# DriverPanel.net
KiCad netlist of a schematic drawn in EAGLE
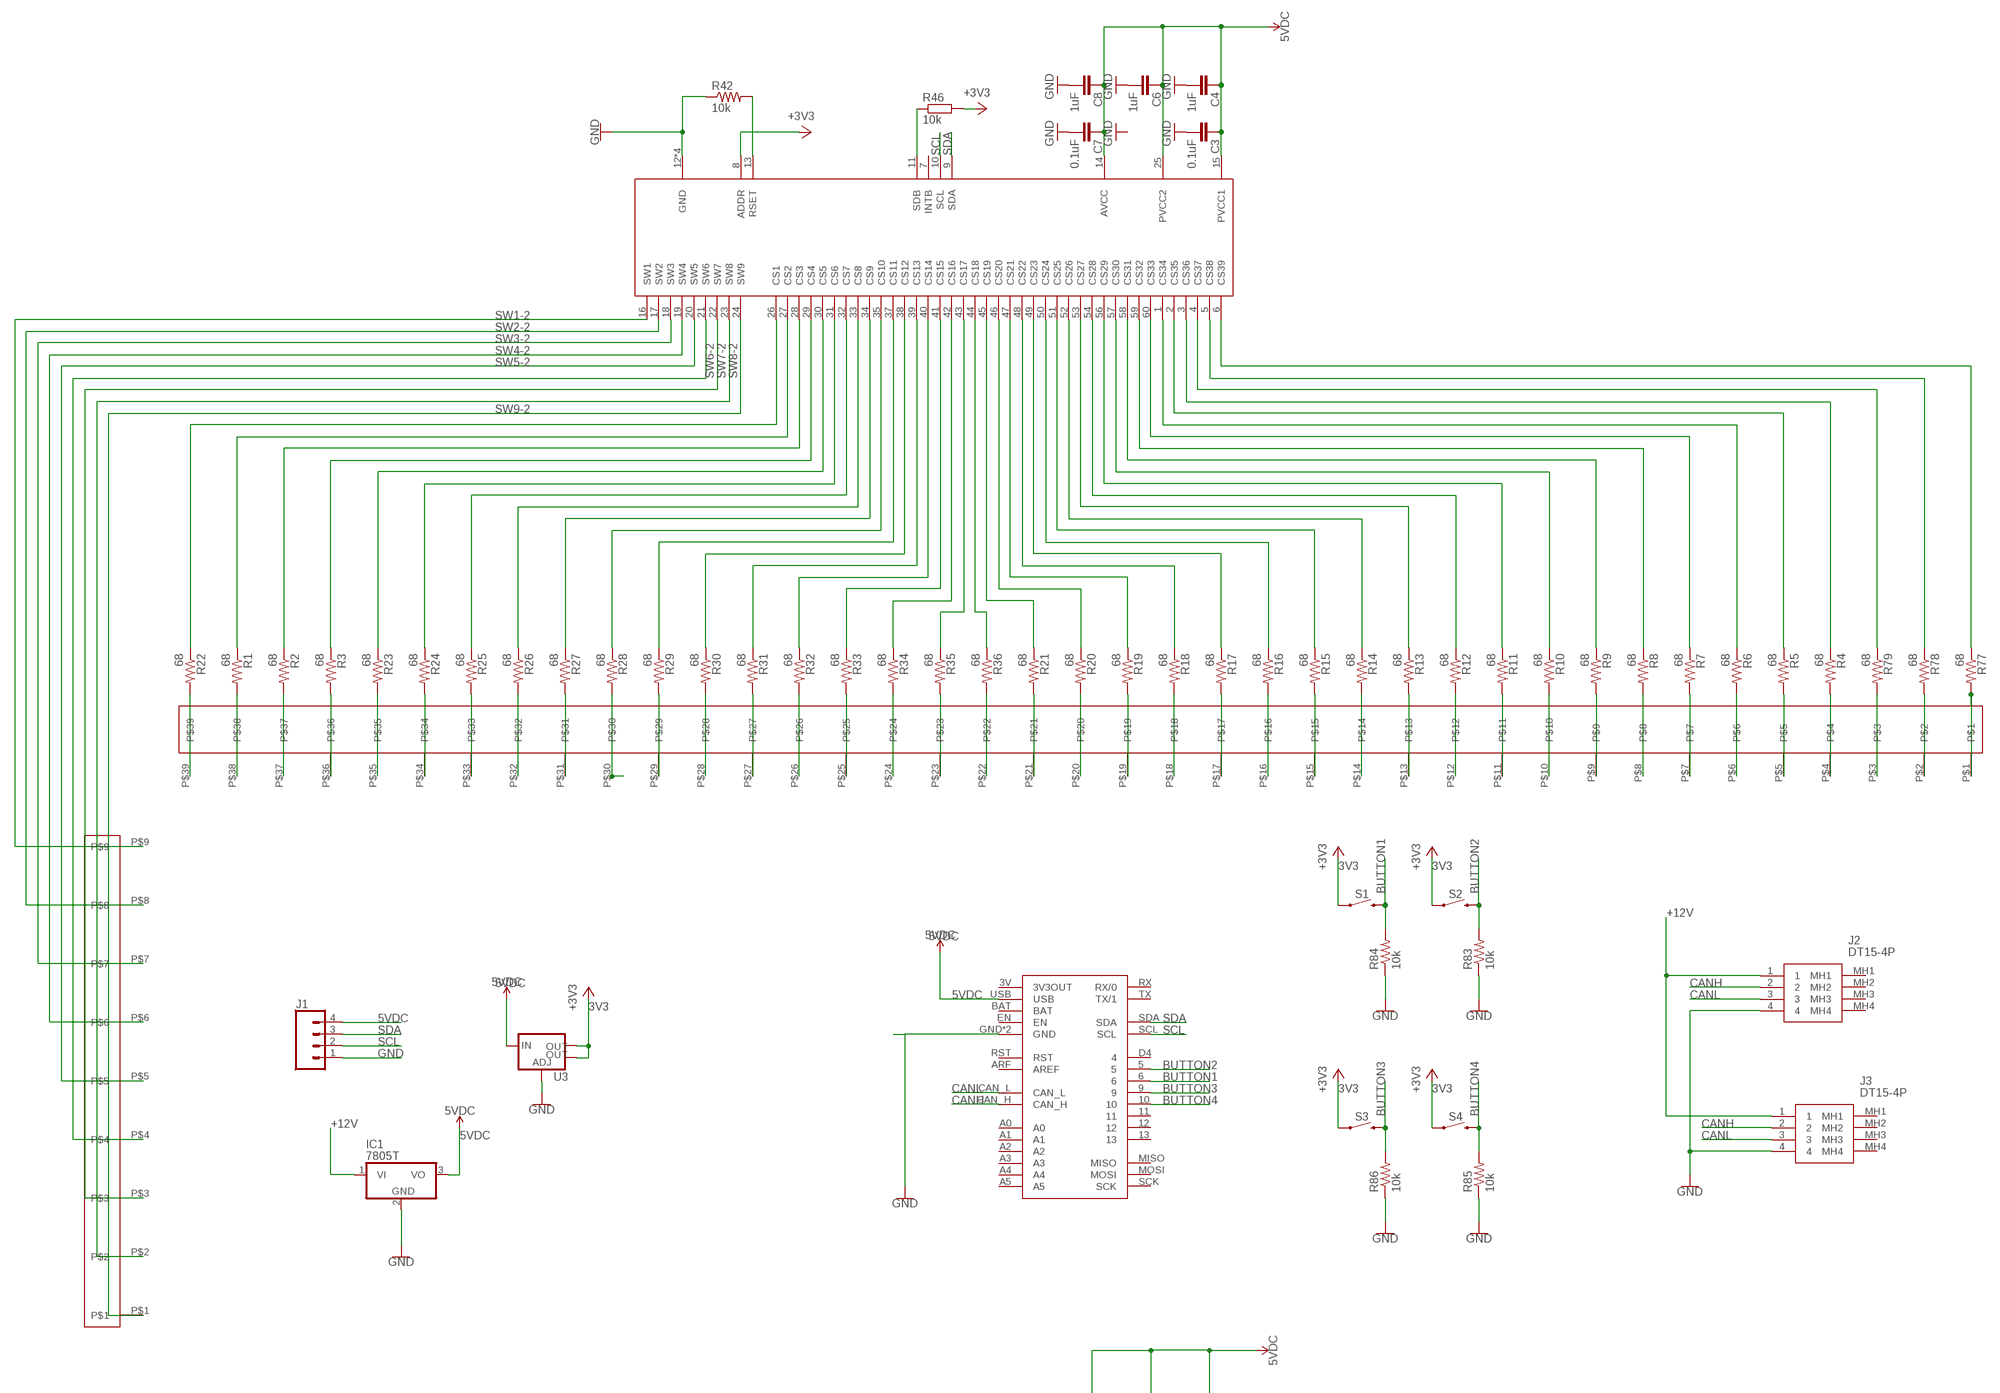
[diagram p0: schematic, sheet 1, part 1 of 2]
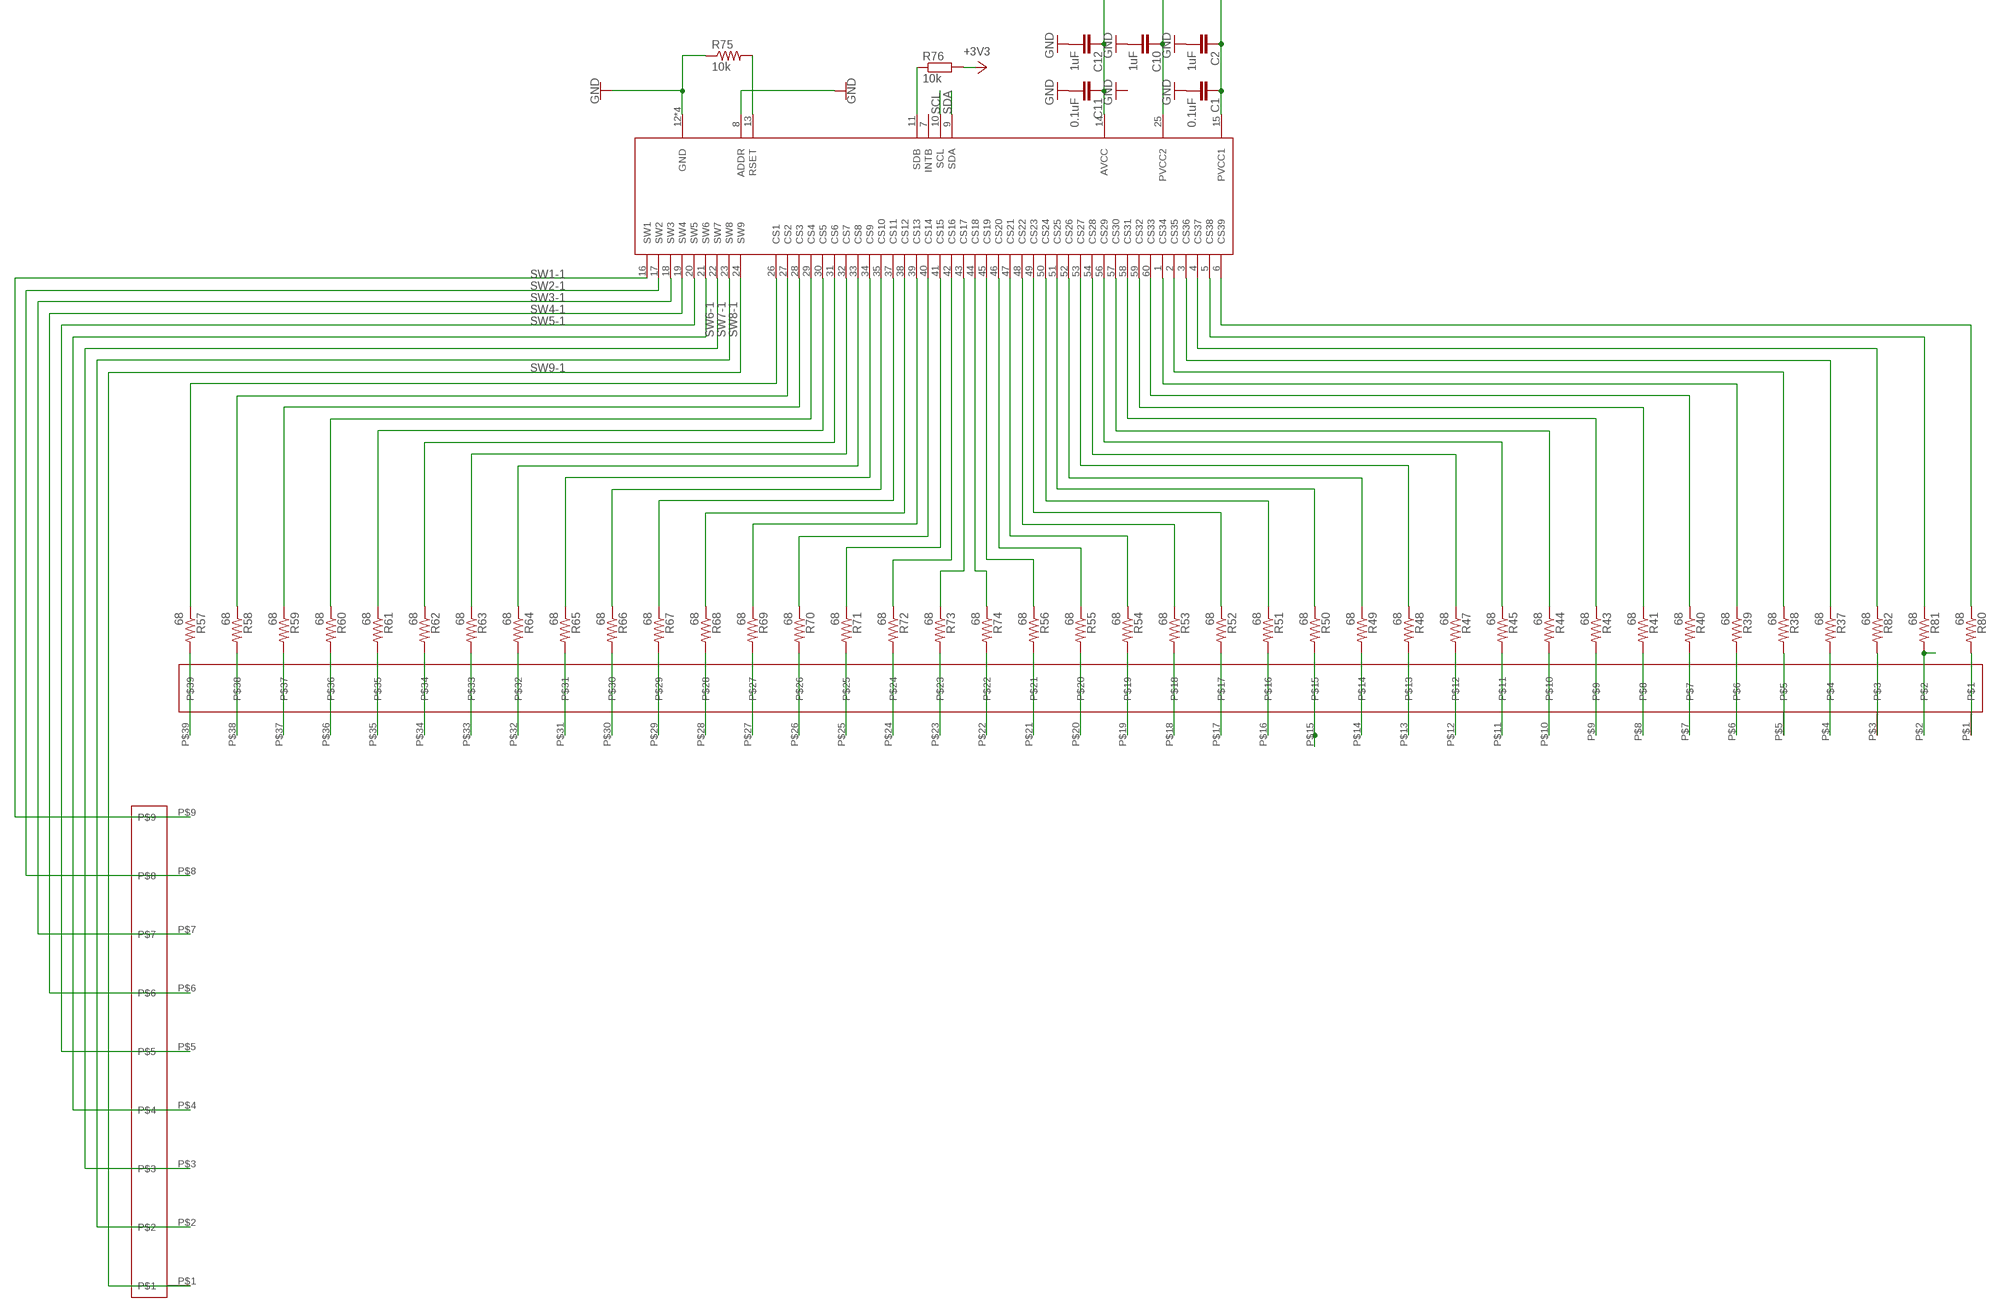
[diagram p1: schematic, sheet 1, part 2 of 2]

(export (version "E")
  (design (tool "Eeschema 10.0.6"))
  (components
    (comp (ref "C1")
      (value "0.1uF")
      (footprint "eagle-import:C0805K")
      (libsource (lib "eagle-import") (part "C-EUC0805K"))
    )
    (comp (ref "C2")
      (value "1uF")
      (footprint "eagle-import:C0805K")
      (libsource (lib "eagle-import") (part "C-EUC0805K"))
    )
    (comp (ref "C3")
      (value "0.1uF")
      (footprint "eagle-import:C0805K")
      (libsource (lib "eagle-import") (part "C-EUC0805K"))
    )
    (comp (ref "C4")
      (value "1uF")
      (footprint "eagle-import:C0805K")
      (libsource (lib "eagle-import") (part "C-EUC0805K"))
    )
    (comp (ref "C6")
      (value "1uF")
      (footprint "eagle-import:C0805K")
      (libsource (lib "eagle-import") (part "C-EUC0805K"))
    )
    (comp (ref "C7")
      (value "0.1uF")
      (footprint "eagle-import:C0805K")
      (libsource (lib "eagle-import") (part "C-EUC0805K"))
    )
    (comp (ref "C8")
      (value "1uF")
      (footprint "eagle-import:C0805K")
      (libsource (lib "eagle-import") (part "C-EUC0805K"))
    )
    (comp (ref "C10")
      (value "1uF")
      (footprint "eagle-import:C0805K")
      (libsource (lib "eagle-import") (part "C-EUC0805K"))
    )
    (comp (ref "C11")
      (value "0.1uF")
      (footprint "eagle-import:C0805K")
      (libsource (lib "eagle-import") (part "C-EUC0805K"))
    )
    (comp (ref "C12")
      (value "1uF")
      (footprint "eagle-import:C0805K")
      (libsource (lib "eagle-import") (part "C-EUC0805K"))
    )
    (comp (ref "IC1")
      (value "7805T")
      (footprint "eagle-import:TO220H")
      (libsource (lib "eagle-import") (part "78T05"))
    )
    (comp (ref "J1")
      (value "CONN_04")
      (footprint "eagle-import:1X04")
      (libsource (lib "eagle-import") (part "CONN_04"))
    )
    (comp (ref "J2")
      (value "DT15-4P")
      (footprint "eagle-import:DT154P")
      (fields (field (name "MOUSER_PART_NUMBER") "571-DT15-4P"))
      (libsource (lib "eagle-import") (part "DT15-4P"))
    )
    (comp (ref "J3")
      (value "DT15-4P")
      (footprint "eagle-import:DT154P")
      (fields (field (name "MOUSER_PART_NUMBER") "571-DT15-4P"))
      (libsource (lib "eagle-import") (part "DT15-4P"))
    )
    (comp (ref "R1")
      (value "68")
      (footprint "eagle-import:R0805")
      (libsource (lib "eagle-import") (part "R-US_R0805"))
    )
    (comp (ref "R2")
      (value "68")
      (footprint "eagle-import:R0805")
      (libsource (lib "eagle-import") (part "R-US_R0805"))
    )
    (comp (ref "R3")
      (value "68")
      (footprint "eagle-import:R0805")
      (libsource (lib "eagle-import") (part "R-US_R0805"))
    )
    (comp (ref "R4")
      (value "68")
      (footprint "eagle-import:R0805")
      (libsource (lib "eagle-import") (part "R-US_R0805"))
    )
    (comp (ref "R5")
      (value "68")
      (footprint "eagle-import:R0805")
      (libsource (lib "eagle-import") (part "R-US_R0805"))
    )
    (comp (ref "R6")
      (value "68")
      (footprint "eagle-import:R0805")
      (libsource (lib "eagle-import") (part "R-US_R0805"))
    )
    (comp (ref "R7")
      (value "68")
      (footprint "eagle-import:R0805")
      (libsource (lib "eagle-import") (part "R-US_R0805"))
    )
    (comp (ref "R8")
      (value "68")
      (footprint "eagle-import:R0805")
      (libsource (lib "eagle-import") (part "R-US_R0805"))
    )
    (comp (ref "R9")
      (value "68")
      (footprint "eagle-import:R0805")
      (libsource (lib "eagle-import") (part "R-US_R0805"))
    )
    (comp (ref "R10")
      (value "68")
      (footprint "eagle-import:R0805")
      (libsource (lib "eagle-import") (part "R-US_R0805"))
    )
    (comp (ref "R11")
      (value "68")
      (footprint "eagle-import:R0805")
      (libsource (lib "eagle-import") (part "R-US_R0805"))
    )
    (comp (ref "R12")
      (value "68")
      (footprint "eagle-import:R0805")
      (libsource (lib "eagle-import") (part "R-US_R0805"))
    )
    (comp (ref "R13")
      (value "68")
      (footprint "eagle-import:R0805")
      (libsource (lib "eagle-import") (part "R-US_R0805"))
    )
    (comp (ref "R14")
      (value "68")
      (footprint "eagle-import:R0805")
      (libsource (lib "eagle-import") (part "R-US_R0805"))
    )
    (comp (ref "R15")
      (value "68")
      (footprint "eagle-import:R0805")
      (libsource (lib "eagle-import") (part "R-US_R0805"))
    )
    (comp (ref "R16")
      (value "68")
      (footprint "eagle-import:R0805")
      (libsource (lib "eagle-import") (part "R-US_R0805"))
    )
    (comp (ref "R17")
      (value "68")
      (footprint "eagle-import:R0805")
      (libsource (lib "eagle-import") (part "R-US_R0805"))
    )
    (comp (ref "R18")
      (value "68")
      (footprint "eagle-import:R0805")
      (libsource (lib "eagle-import") (part "R-US_R0805"))
    )
    (comp (ref "R19")
      (value "68")
      (footprint "eagle-import:R0805")
      (libsource (lib "eagle-import") (part "R-US_R0805"))
    )
    (comp (ref "R20")
      (value "68")
      (footprint "eagle-import:R0805")
      (libsource (lib "eagle-import") (part "R-US_R0805"))
    )
    (comp (ref "R21")
      (value "68")
      (footprint "eagle-import:R0805")
      (libsource (lib "eagle-import") (part "R-US_R0805"))
    )
    (comp (ref "R22")
      (value "68")
      (footprint "eagle-import:R0805")
      (libsource (lib "eagle-import") (part "R-US_R0805"))
    )
    (comp (ref "R23")
      (value "68")
      (footprint "eagle-import:R0805")
      (libsource (lib "eagle-import") (part "R-US_R0805"))
    )
    (comp (ref "R24")
      (value "68")
      (footprint "eagle-import:R0805")
      (libsource (lib "eagle-import") (part "R-US_R0805"))
    )
    (comp (ref "R25")
      (value "68")
      (footprint "eagle-import:R0805")
      (libsource (lib "eagle-import") (part "R-US_R0805"))
    )
    (comp (ref "R26")
      (value "68")
      (footprint "eagle-import:R0805")
      (libsource (lib "eagle-import") (part "R-US_R0805"))
    )
    (comp (ref "R27")
      (value "68")
      (footprint "eagle-import:R0805")
      (libsource (lib "eagle-import") (part "R-US_R0805"))
    )
    (comp (ref "R28")
      (value "68")
      (footprint "eagle-import:R0805")
      (libsource (lib "eagle-import") (part "R-US_R0805"))
    )
    (comp (ref "R29")
      (value "68")
      (footprint "eagle-import:R0805")
      (libsource (lib "eagle-import") (part "R-US_R0805"))
    )
    (comp (ref "R30")
      (value "68")
      (footprint "eagle-import:R0805")
      (libsource (lib "eagle-import") (part "R-US_R0805"))
    )
    (comp (ref "R31")
      (value "68")
      (footprint "eagle-import:R0805")
      (libsource (lib "eagle-import") (part "R-US_R0805"))
    )
    (comp (ref "R32")
      (value "68")
      (footprint "eagle-import:R0805")
      (libsource (lib "eagle-import") (part "R-US_R0805"))
    )
    (comp (ref "R33")
      (value "68")
      (footprint "eagle-import:R0805")
      (libsource (lib "eagle-import") (part "R-US_R0805"))
    )
    (comp (ref "R34")
      (value "68")
      (footprint "eagle-import:R0805")
      (libsource (lib "eagle-import") (part "R-US_R0805"))
    )
    (comp (ref "R35")
      (value "68")
      (footprint "eagle-import:R0805")
      (libsource (lib "eagle-import") (part "R-US_R0805"))
    )
    (comp (ref "R36")
      (value "68")
      (footprint "eagle-import:R0805")
      (libsource (lib "eagle-import") (part "R-US_R0805"))
    )
    (comp (ref "R37")
      (value "68")
      (footprint "eagle-import:R0805")
      (libsource (lib "eagle-import") (part "R-US_R0805"))
    )
    (comp (ref "R38")
      (value "68")
      (footprint "eagle-import:R0805")
      (libsource (lib "eagle-import") (part "R-US_R0805"))
    )
    (comp (ref "R39")
      (value "68")
      (footprint "eagle-import:R0805")
      (libsource (lib "eagle-import") (part "R-US_R0805"))
    )
    (comp (ref "R40")
      (value "68")
      (footprint "eagle-import:R0805")
      (libsource (lib "eagle-import") (part "R-US_R0805"))
    )
    (comp (ref "R41")
      (value "68")
      (footprint "eagle-import:R0805")
      (libsource (lib "eagle-import") (part "R-US_R0805"))
    )
    (comp (ref "R42")
      (value "10k")
      (footprint "eagle-import:R0805")
      (libsource (lib "eagle-import") (part "R-US_R0805"))
    )
    (comp (ref "R43")
      (value "68")
      (footprint "eagle-import:R0805")
      (libsource (lib "eagle-import") (part "R-US_R0805"))
    )
    (comp (ref "R44")
      (value "68")
      (footprint "eagle-import:R0805")
      (libsource (lib "eagle-import") (part "R-US_R0805"))
    )
    (comp (ref "R45")
      (value "68")
      (footprint "eagle-import:R0805")
      (libsource (lib "eagle-import") (part "R-US_R0805"))
    )
    (comp (ref "R46")
      (value "10k")
      (footprint "eagle-import:R0805")
      (libsource (lib "eagle-import") (part "R-EU_R0805"))
    )
    (comp (ref "R47")
      (value "68")
      (footprint "eagle-import:R0805")
      (libsource (lib "eagle-import") (part "R-US_R0805"))
    )
    (comp (ref "R48")
      (value "68")
      (footprint "eagle-import:R0805")
      (libsource (lib "eagle-import") (part "R-US_R0805"))
    )
    (comp (ref "R49")
      (value "68")
      (footprint "eagle-import:R0805")
      (libsource (lib "eagle-import") (part "R-US_R0805"))
    )
    (comp (ref "R50")
      (value "68")
      (footprint "eagle-import:R0805")
      (libsource (lib "eagle-import") (part "R-US_R0805"))
    )
    (comp (ref "R51")
      (value "68")
      (footprint "eagle-import:R0805")
      (libsource (lib "eagle-import") (part "R-US_R0805"))
    )
    (comp (ref "R52")
      (value "68")
      (footprint "eagle-import:R0805")
      (libsource (lib "eagle-import") (part "R-US_R0805"))
    )
    (comp (ref "R53")
      (value "68")
      (footprint "eagle-import:R0805")
      (libsource (lib "eagle-import") (part "R-US_R0805"))
    )
    (comp (ref "R54")
      (value "68")
      (footprint "eagle-import:R0805")
      (libsource (lib "eagle-import") (part "R-US_R0805"))
    )
    (comp (ref "R55")
      (value "68")
      (footprint "eagle-import:R0805")
      (libsource (lib "eagle-import") (part "R-US_R0805"))
    )
    (comp (ref "R56")
      (value "68")
      (footprint "eagle-import:R0805")
      (libsource (lib "eagle-import") (part "R-US_R0805"))
    )
    (comp (ref "R57")
      (value "68")
      (footprint "eagle-import:R0805")
      (libsource (lib "eagle-import") (part "R-US_R0805"))
    )
    (comp (ref "R58")
      (value "68")
      (footprint "eagle-import:R0805")
      (libsource (lib "eagle-import") (part "R-US_R0805"))
    )
    (comp (ref "R59")
      (value "68")
      (footprint "eagle-import:R0805")
      (libsource (lib "eagle-import") (part "R-US_R0805"))
    )
    (comp (ref "R60")
      (value "68")
      (footprint "eagle-import:R0805")
      (libsource (lib "eagle-import") (part "R-US_R0805"))
    )
    (comp (ref "R61")
      (value "68")
      (footprint "eagle-import:R0805")
      (libsource (lib "eagle-import") (part "R-US_R0805"))
    )
    (comp (ref "R62")
      (value "68")
      (footprint "eagle-import:R0805")
      (libsource (lib "eagle-import") (part "R-US_R0805"))
    )
    (comp (ref "R63")
      (value "68")
      (footprint "eagle-import:R0805")
      (libsource (lib "eagle-import") (part "R-US_R0805"))
    )
    (comp (ref "R64")
      (value "68")
      (footprint "eagle-import:R0805")
      (libsource (lib "eagle-import") (part "R-US_R0805"))
    )
    (comp (ref "R65")
      (value "68")
      (footprint "eagle-import:R0805")
      (libsource (lib "eagle-import") (part "R-US_R0805"))
    )
    (comp (ref "R66")
      (value "68")
      (footprint "eagle-import:R0805")
      (libsource (lib "eagle-import") (part "R-US_R0805"))
    )
    (comp (ref "R67")
      (value "68")
      (footprint "eagle-import:R0805")
      (libsource (lib "eagle-import") (part "R-US_R0805"))
    )
    (comp (ref "R68")
      (value "68")
      (footprint "eagle-import:R0805")
      (libsource (lib "eagle-import") (part "R-US_R0805"))
    )
    (comp (ref "R69")
      (value "68")
      (footprint "eagle-import:R0805")
      (libsource (lib "eagle-import") (part "R-US_R0805"))
    )
    (comp (ref "R70")
      (value "68")
      (footprint "eagle-import:R0805")
      (libsource (lib "eagle-import") (part "R-US_R0805"))
    )
    (comp (ref "R71")
      (value "68")
      (footprint "eagle-import:R0805")
      (libsource (lib "eagle-import") (part "R-US_R0805"))
    )
    (comp (ref "R72")
      (value "68")
      (footprint "eagle-import:R0805")
      (libsource (lib "eagle-import") (part "R-US_R0805"))
    )
    (comp (ref "R73")
      (value "68")
      (footprint "eagle-import:R0805")
      (libsource (lib "eagle-import") (part "R-US_R0805"))
    )
    (comp (ref "R74")
      (value "68")
      (footprint "eagle-import:R0805")
      (libsource (lib "eagle-import") (part "R-US_R0805"))
    )
    (comp (ref "R75")
      (value "10k")
      (footprint "eagle-import:R0805")
      (libsource (lib "eagle-import") (part "R-US_R0805"))
    )
    (comp (ref "R76")
      (value "10k")
      (footprint "eagle-import:R0805")
      (libsource (lib "eagle-import") (part "R-EU_R0805"))
    )
    (comp (ref "R77")
      (value "68")
      (footprint "eagle-import:R0805")
      (libsource (lib "eagle-import") (part "R-US_R0805"))
    )
    (comp (ref "R78")
      (value "68")
      (footprint "eagle-import:R0805")
      (libsource (lib "eagle-import") (part "R-US_R0805"))
    )
    (comp (ref "R79")
      (value "68")
      (footprint "eagle-import:R0805")
      (libsource (lib "eagle-import") (part "R-US_R0805"))
    )
    (comp (ref "R80")
      (value "68")
      (footprint "eagle-import:R0805")
      (libsource (lib "eagle-import") (part "R-US_R0805"))
    )
    (comp (ref "R81")
      (value "68")
      (footprint "eagle-import:R0805")
      (libsource (lib "eagle-import") (part "R-US_R0805"))
    )
    (comp (ref "R82")
      (value "68")
      (footprint "eagle-import:R0805")
      (libsource (lib "eagle-import") (part "R-US_R0805"))
    )
    (comp (ref "R83")
      (value "10k")
      (footprint "eagle-import:R0805")
      (libsource (lib "eagle-import") (part "R-US_R0805"))
    )
    (comp (ref "R84")
      (value "10k")
      (footprint "eagle-import:R0805")
      (libsource (lib "eagle-import") (part "R-US_R0805"))
    )
    (comp (ref "R85")
      (value "10k")
      (footprint "eagle-import:R0805")
      (libsource (lib "eagle-import") (part "R-US_R0805"))
    )
    (comp (ref "R86")
      (value "10k")
      (footprint "eagle-import:R0805")
      (libsource (lib "eagle-import") (part "R-US_R0805"))
    )
    (comp (ref "S1")
      (value "MOMENTARY-SWITCH-SPST-PTH-6.0MM")
      (footprint "eagle-import:TACTILE_SWITCH_PTH_6.0MM")
      (libsource (lib "eagle-import") (part "MOMENTARY-SWITCH-SPST-PTH-6.0MM"))
    )
    (comp (ref "S2")
      (value "MOMENTARY-SWITCH-SPST-PTH-6.0MM")
      (footprint "eagle-import:TACTILE_SWITCH_PTH_6.0MM")
      (libsource (lib "eagle-import") (part "MOMENTARY-SWITCH-SPST-PTH-6.0MM"))
    )
    (comp (ref "S3")
      (value "MOMENTARY-SWITCH-SPST-PTH-6.0MM")
      (footprint "eagle-import:TACTILE_SWITCH_PTH_6.0MM")
      (libsource (lib "eagle-import") (part "MOMENTARY-SWITCH-SPST-PTH-6.0MM"))
    )
    (comp (ref "S4")
      (value "MOMENTARY-SWITCH-SPST-PTH-6.0MM")
      (footprint "eagle-import:TACTILE_SWITCH_PTH_6.0MM")
      (libsource (lib "eagle-import") (part "MOMENTARY-SWITCH-SPST-PTH-6.0MM"))
    )
    (comp (ref "U$1")
      (value "39COLUMN")
      (footprint "eagle-import:COLUMNS")
      (libsource (lib "eagle-import") (part "39COLUMN"))
    )
    (comp (ref "U$2")
      (value "39COLUMN")
      (footprint "eagle-import:COLUMNS")
      (libsource (lib "eagle-import") (part "39COLUMN"))
    )
    (comp (ref "U$3")
      (value "9ROW")
      (footprint "eagle-import:ROWS")
      (libsource (lib "eagle-import") (part "9ROW"))
    )
    (comp (ref "U$4")
      (value "9ROW")
      (footprint "eagle-import:ROWS")
      (libsource (lib "eagle-import") (part "9ROW"))
    )
    (comp (ref "U$5")
      (value "FEATHERM4CAN")
      (footprint "eagle-import:FEATHERCAN")
      (libsource (lib "eagle-import") (part "FEATHERM4CAN"))
    )
    (comp (ref "U1")
      (value "IS31FL3741_QFN60")
      (footprint "eagle-import:QFN60")
      (libsource (lib "eagle-import") (part "IS31FL3741_QFN60"))
    )
    (comp (ref "U2")
      (value "IS31FL3741_QFN60")
      (footprint "eagle-import:QFN60")
      (libsource (lib "eagle-import") (part "IS31FL3741_QFN60"))
    )
    (comp (ref "U3")
      (value "V_REG_LM1117SOT223")
      (footprint "eagle-import:SOT223")
      (libsource (lib "eagle-import") (part "V_REG_LM1117SOT223"))
    )
  )
  (nets
    (net (code "1") (name "+3V3") (class "Default")
      (node (ref "R46") (pin "2") (pinfunction "2_2") (pintype "passive"))
      (node (ref "R76") (pin "2") (pinfunction "2_2") (pintype "passive"))
      (node (ref "S1") (pin "1") (pinfunction "1_1") (pintype "passive"))
      (node (ref "S2") (pin "1") (pinfunction "1_1") (pintype "passive"))
      (node (ref "S3") (pin "1") (pinfunction "1_1") (pintype "passive"))
      (node (ref "S4") (pin "1") (pinfunction "1_1") (pintype "passive"))
      (node (ref "U1") (pin "8") (pinfunction "ADDR_8") (pintype "bidirectional"))
      (node (ref "U3") (pin "2") (pinfunction "OUT_2") (pintype "output"))
      (node (ref "U3") (pin "4") (pinfunction "OUT_4") (pintype "output"))
    )
    (net (code "2") (name "/+12V") (class "Default")
      (node (ref "IC1") (pin "1") (pinfunction "VI_1") (pintype "input"))
      (node (ref "J2") (pin "1") (pinfunction "1_1") (pintype "bidirectional"))
      (node (ref "J3") (pin "1") (pinfunction "1_1") (pintype "bidirectional"))
    )
    (net (code "3") (name "/BUTTON1") (class "Default")
      (node (ref "R84") (pin "2") (pinfunction "2_2") (pintype "passive"))
      (node (ref "S1") (pin "3") (pinfunction "2_3") (pintype "passive"))
      (node (ref "U$5") (pin "6") (pinfunction "6_6") (pintype "bidirectional"))
    )
    (net (code "4") (name "/BUTTON2") (class "Default")
      (node (ref "R83") (pin "2") (pinfunction "2_2") (pintype "passive"))
      (node (ref "S2") (pin "3") (pinfunction "2_3") (pintype "passive"))
      (node (ref "U$5") (pin "5") (pinfunction "5_5") (pintype "bidirectional"))
    )
    (net (code "5") (name "/BUTTON3") (class "Default")
      (node (ref "R86") (pin "2") (pinfunction "2_2") (pintype "passive"))
      (node (ref "S3") (pin "3") (pinfunction "2_3") (pintype "passive"))
      (node (ref "U$5") (pin "9") (pinfunction "9_9") (pintype "bidirectional"))
    )
    (net (code "6") (name "/BUTTON4") (class "Default")
      (node (ref "R85") (pin "2") (pinfunction "2_2") (pintype "passive"))
      (node (ref "S4") (pin "3") (pinfunction "2_3") (pintype "passive"))
      (node (ref "U$5") (pin "10") (pinfunction "10_10") (pintype "bidirectional"))
    )
    (net (code "7") (name "/CANH") (class "Default")
      (node (ref "J2") (pin "2") (pinfunction "2_2") (pintype "bidirectional"))
      (node (ref "J3") (pin "2") (pinfunction "2_2") (pintype "bidirectional"))
      (node (ref "U$5") (pin "CAN_H") (pinfunction "CAN_H_CAN_H") (pintype "bidirectional"))
    )
    (net (code "8") (name "/CANL") (class "Default")
      (node (ref "J2") (pin "3") (pinfunction "3_3") (pintype "bidirectional"))
      (node (ref "J3") (pin "3") (pinfunction "3_3") (pintype "bidirectional"))
      (node (ref "U$5") (pin "CAN_L") (pinfunction "CAN_L_CAN_L") (pintype "bidirectional"))
    )
    (net (code "9") (name "/SCL") (class "Default")
      (node (ref "J1") (pin "2") (pinfunction "2_2") (pintype "passive"))
      (node (ref "U$5") (pin "SCL") (pinfunction "SCL_SCL") (pintype "bidirectional"))
      (node (ref "U1") (pin "10") (pinfunction "SCL_10") (pintype "bidirectional"))
      (node (ref "U2") (pin "10") (pinfunction "SCL_10") (pintype "bidirectional"))
    )
    (net (code "10") (name "/SDA") (class "Default")
      (node (ref "J1") (pin "3") (pinfunction "3_3") (pintype "passive"))
      (node (ref "U$5") (pin "SDA") (pinfunction "SDA_SDA") (pintype "bidirectional"))
      (node (ref "U1") (pin "9") (pinfunction "SDA_9") (pintype "bidirectional"))
      (node (ref "U2") (pin "9") (pinfunction "SDA_9") (pintype "bidirectional"))
    )
    (net (code "11") (name "/SW1-1") (class "Default")
      (node (ref "U$3") (pin "P$9") (pinfunction "P$9_P$9") (pintype "bidirectional"))
      (node (ref "U2") (pin "16") (pinfunction "SW1_16") (pintype "bidirectional"))
    )
    (net (code "12") (name "/SW1-2") (class "Default")
      (node (ref "U$4") (pin "P$9") (pinfunction "P$9_P$9") (pintype "bidirectional"))
      (node (ref "U1") (pin "16") (pinfunction "SW1_16") (pintype "bidirectional"))
    )
    (net (code "13") (name "/SW2-1") (class "Default")
      (node (ref "U$3") (pin "P$8") (pinfunction "P$8_P$8") (pintype "bidirectional"))
      (node (ref "U2") (pin "17") (pinfunction "SW2_17") (pintype "bidirectional"))
    )
    (net (code "14") (name "/SW2-2") (class "Default")
      (node (ref "U$4") (pin "P$8") (pinfunction "P$8_P$8") (pintype "bidirectional"))
      (node (ref "U1") (pin "17") (pinfunction "SW2_17") (pintype "bidirectional"))
    )
    (net (code "15") (name "/SW3-1") (class "Default")
      (node (ref "U$3") (pin "P$7") (pinfunction "P$7_P$7") (pintype "bidirectional"))
      (node (ref "U2") (pin "18") (pinfunction "SW3_18") (pintype "bidirectional"))
    )
    (net (code "16") (name "/SW3-2") (class "Default")
      (node (ref "U$4") (pin "P$7") (pinfunction "P$7_P$7") (pintype "bidirectional"))
      (node (ref "U1") (pin "18") (pinfunction "SW3_18") (pintype "bidirectional"))
    )
    (net (code "17") (name "/SW4-1") (class "Default")
      (node (ref "U$3") (pin "P$6") (pinfunction "P$6_P$6") (pintype "bidirectional"))
      (node (ref "U2") (pin "19") (pinfunction "SW4_19") (pintype "bidirectional"))
    )
    (net (code "18") (name "/SW4-2") (class "Default")
      (node (ref "U$4") (pin "P$6") (pinfunction "P$6_P$6") (pintype "bidirectional"))
      (node (ref "U1") (pin "19") (pinfunction "SW4_19") (pintype "bidirectional"))
    )
    (net (code "19") (name "/SW5-1") (class "Default")
      (node (ref "U$3") (pin "P$5") (pinfunction "P$5_P$5") (pintype "bidirectional"))
      (node (ref "U2") (pin "20") (pinfunction "SW5_20") (pintype "bidirectional"))
    )
    (net (code "20") (name "/SW5-2") (class "Default")
      (node (ref "U$4") (pin "P$5") (pinfunction "P$5_P$5") (pintype "bidirectional"))
      (node (ref "U1") (pin "20") (pinfunction "SW5_20") (pintype "bidirectional"))
    )
    (net (code "21") (name "/SW6-1") (class "Default")
      (node (ref "U$3") (pin "P$4") (pinfunction "P$4_P$4") (pintype "bidirectional"))
      (node (ref "U2") (pin "21") (pinfunction "SW6_21") (pintype "bidirectional"))
    )
    (net (code "22") (name "/SW6-2") (class "Default")
      (node (ref "U$4") (pin "P$4") (pinfunction "P$4_P$4") (pintype "bidirectional"))
      (node (ref "U1") (pin "21") (pinfunction "SW6_21") (pintype "bidirectional"))
    )
    (net (code "23") (name "/SW7-1") (class "Default")
      (node (ref "U$3") (pin "P$3") (pinfunction "P$3_P$3") (pintype "bidirectional"))
      (node (ref "U2") (pin "22") (pinfunction "SW7_22") (pintype "bidirectional"))
    )
    (net (code "24") (name "/SW7-2") (class "Default")
      (node (ref "U$4") (pin "P$3") (pinfunction "P$3_P$3") (pintype "bidirectional"))
      (node (ref "U1") (pin "22") (pinfunction "SW7_22") (pintype "bidirectional"))
    )
    (net (code "25") (name "/SW8-1") (class "Default")
      (node (ref "U$3") (pin "P$2") (pinfunction "P$2_P$2") (pintype "bidirectional"))
      (node (ref "U2") (pin "23") (pinfunction "SW8_23") (pintype "bidirectional"))
    )
    (net (code "26") (name "/SW8-2") (class "Default")
      (node (ref "U$4") (pin "P$2") (pinfunction "P$2_P$2") (pintype "bidirectional"))
      (node (ref "U1") (pin "23") (pinfunction "SW8_23") (pintype "bidirectional"))
    )
    (net (code "27") (name "/SW9-1") (class "Default")
      (node (ref "U$3") (pin "P$1") (pinfunction "P$1_P$1") (pintype "bidirectional"))
      (node (ref "U2") (pin "24") (pinfunction "SW9_24") (pintype "bidirectional"))
    )
    (net (code "28") (name "/SW9-2") (class "Default")
      (node (ref "U$4") (pin "P$1") (pinfunction "P$1_P$1") (pintype "bidirectional"))
      (node (ref "U1") (pin "24") (pinfunction "SW9_24") (pintype "bidirectional"))
    )
    (net (code "29") (name "5VDC") (class "Default")
      (node (ref "C1") (pin "1") (pinfunction "1_1") (pintype "passive"))
      (node (ref "C10") (pin "1") (pinfunction "1_1") (pintype "passive"))
      (node (ref "C11") (pin "1") (pinfunction "1_1") (pintype "passive"))
      (node (ref "C12") (pin "1") (pinfunction "1_1") (pintype "passive"))
      (node (ref "C2") (pin "1") (pinfunction "1_1") (pintype "passive"))
      (node (ref "C3") (pin "1") (pinfunction "1_1") (pintype "passive"))
      (node (ref "C4") (pin "1") (pinfunction "1_1") (pintype "passive"))
      (node (ref "C6") (pin "1") (pinfunction "1_1") (pintype "passive"))
      (node (ref "C7") (pin "1") (pinfunction "1_1") (pintype "passive"))
      (node (ref "C8") (pin "1") (pinfunction "1_1") (pintype "passive"))
      (node (ref "IC1") (pin "3") (pinfunction "VO_3") (pintype "passive"))
      (node (ref "J1") (pin "4") (pinfunction "4_4") (pintype "passive"))
      (node (ref "U$5") (pin "USB") (pinfunction "USB_USB") (pintype "bidirectional"))
      (node (ref "U1") (pin "14") (pinfunction "AVCC_14") (pintype "bidirectional"))
      (node (ref "U1") (pin "15") (pinfunction "PVCC1_15") (pintype "bidirectional"))
      (node (ref "U1") (pin "25") (pinfunction "PVCC2_25") (pintype "bidirectional"))
      (node (ref "U2") (pin "14") (pinfunction "AVCC_14") (pintype "bidirectional"))
      (node (ref "U2") (pin "15") (pinfunction "PVCC1_15") (pintype "bidirectional"))
      (node (ref "U2") (pin "25") (pinfunction "PVCC2_25") (pintype "bidirectional"))
      (node (ref "U3") (pin "3") (pinfunction "IN_3") (pintype "input"))
    )
    (net (code "30") (name "GND") (class "Default")
      (node (ref "C1") (pin "2") (pinfunction "2_2") (pintype "passive"))
      (node (ref "C10") (pin "2") (pinfunction "2_2") (pintype "passive"))
      (node (ref "C11") (pin "2") (pinfunction "2_2") (pintype "passive"))
      (node (ref "C12") (pin "2") (pinfunction "2_2") (pintype "passive"))
      (node (ref "C2") (pin "2") (pinfunction "2_2") (pintype "passive"))
      (node (ref "C3") (pin "2") (pinfunction "2_2") (pintype "passive"))
      (node (ref "C4") (pin "2") (pinfunction "2_2") (pintype "passive"))
      (node (ref "C6") (pin "2") (pinfunction "2_2") (pintype "passive"))
      (node (ref "C7") (pin "2") (pinfunction "2_2") (pintype "passive"))
      (node (ref "C8") (pin "2") (pinfunction "2_2") (pintype "passive"))
      (node (ref "IC1") (pin "2") (pinfunction "GND_2") (pintype "passive"))
      (node (ref "J1") (pin "1") (pinfunction "1_1") (pintype "passive"))
      (node (ref "J2") (pin "4") (pinfunction "4_4") (pintype "bidirectional"))
      (node (ref "J3") (pin "4") (pinfunction "4_4") (pintype "bidirectional"))
      (node (ref "R42") (pin "1") (pinfunction "1_1") (pintype "passive"))
      (node (ref "R75") (pin "1") (pinfunction "1_1") (pintype "passive"))
      (node (ref "R83") (pin "1") (pinfunction "1_1") (pintype "passive"))
      (node (ref "R84") (pin "1") (pinfunction "1_1") (pintype "passive"))
      (node (ref "R85") (pin "1") (pinfunction "1_1") (pintype "passive"))
      (node (ref "R86") (pin "1") (pinfunction "1_1") (pintype "passive"))
      (node (ref "U$5") (pin "GND") (pinfunction "GND_GND") (pintype "bidirectional"))
      (node (ref "U$5") (pin "GND2") (pinfunction "GND_GND2") (pintype "bidirectional"))
      (node (ref "U1") (pin "12") (pinfunction "GND_12") (pintype "bidirectional"))
      (node (ref "U1") (pin "36") (pinfunction "GND_36") (pintype "bidirectional"))
      (node (ref "U1") (pin "55") (pinfunction "GND_55") (pintype "bidirectional"))
      (node (ref "U1") (pin "PAD") (pinfunction "GND_PAD") (pintype "bidirectional"))
      (node (ref "U2") (pin "12") (pinfunction "GND_12") (pintype "bidirectional"))
      (node (ref "U2") (pin "36") (pinfunction "GND_36") (pintype "bidirectional"))
      (node (ref "U2") (pin "55") (pinfunction "GND_55") (pintype "bidirectional"))
      (node (ref "U2") (pin "8") (pinfunction "ADDR_8") (pintype "bidirectional"))
      (node (ref "U2") (pin "PAD") (pinfunction "GND_PAD") (pintype "bidirectional"))
      (node (ref "U3") (pin "1") (pinfunction "ADJ_1") (pintype "input"))
    )
    (net (code "31") (name "Net-(R1-Pad2)") (class "Default")
      (node (ref "R1") (pin "2") (pinfunction "2_2") (pintype "passive"))
      (node (ref "U$1") (pin "P$38") (pinfunction "P$38_P$38") (pintype "bidirectional"))
    )
    (net (code "32") (name "Net-(R2-Pad2)") (class "Default")
      (node (ref "R2") (pin "2") (pinfunction "2_2") (pintype "passive"))
      (node (ref "U$1") (pin "P$37") (pinfunction "P$37_P$37") (pintype "bidirectional"))
    )
    (net (code "33") (name "Net-(R3-Pad2)") (class "Default")
      (node (ref "R3") (pin "2") (pinfunction "2_2") (pintype "passive"))
      (node (ref "U$1") (pin "P$36") (pinfunction "P$36_P$36") (pintype "bidirectional"))
    )
    (net (code "34") (name "Net-(R4-Pad2)") (class "Default")
      (node (ref "R4") (pin "2") (pinfunction "2_2") (pintype "passive"))
      (node (ref "U$1") (pin "P$4") (pinfunction "P$4_P$4") (pintype "bidirectional"))
    )
    (net (code "35") (name "Net-(R5-Pad2)") (class "Default")
      (node (ref "R5") (pin "2") (pinfunction "2_2") (pintype "passive"))
      (node (ref "U$1") (pin "P$5") (pinfunction "P$5_P$5") (pintype "bidirectional"))
    )
    (net (code "36") (name "Net-(R6-Pad2)") (class "Default")
      (node (ref "R6") (pin "2") (pinfunction "2_2") (pintype "passive"))
      (node (ref "U$1") (pin "P$6") (pinfunction "P$6_P$6") (pintype "bidirectional"))
    )
    (net (code "37") (name "Net-(R7-Pad2)") (class "Default")
      (node (ref "R7") (pin "2") (pinfunction "2_2") (pintype "passive"))
      (node (ref "U$1") (pin "P$7") (pinfunction "P$7_P$7") (pintype "bidirectional"))
    )
    (net (code "38") (name "Net-(R8-Pad2)") (class "Default")
      (node (ref "R8") (pin "2") (pinfunction "2_2") (pintype "passive"))
      (node (ref "U$1") (pin "P$8") (pinfunction "P$8_P$8") (pintype "bidirectional"))
    )
    (net (code "39") (name "Net-(R9-Pad2)") (class "Default")
      (node (ref "R9") (pin "2") (pinfunction "2_2") (pintype "passive"))
      (node (ref "U$1") (pin "P$9") (pinfunction "P$9_P$9") (pintype "bidirectional"))
    )
    (net (code "40") (name "Net-(R10-Pad2)") (class "Default")
      (node (ref "R10") (pin "2") (pinfunction "2_2") (pintype "passive"))
      (node (ref "U$1") (pin "P$10") (pinfunction "P$10_P$10") (pintype "bidirectional"))
    )
    (net (code "41") (name "Net-(R11-Pad2)") (class "Default")
      (node (ref "R11") (pin "2") (pinfunction "2_2") (pintype "passive"))
      (node (ref "U$1") (pin "P$11") (pinfunction "P$11_P$11") (pintype "bidirectional"))
    )
    (net (code "42") (name "Net-(R12-Pad2)") (class "Default")
      (node (ref "R12") (pin "2") (pinfunction "2_2") (pintype "passive"))
      (node (ref "U$1") (pin "P$12") (pinfunction "P$12_P$12") (pintype "bidirectional"))
    )
    (net (code "43") (name "Net-(R13-Pad2)") (class "Default")
      (node (ref "R13") (pin "2") (pinfunction "2_2") (pintype "passive"))
      (node (ref "U$1") (pin "P$13") (pinfunction "P$13_P$13") (pintype "bidirectional"))
    )
    (net (code "44") (name "Net-(R14-Pad2)") (class "Default")
      (node (ref "R14") (pin "2") (pinfunction "2_2") (pintype "passive"))
      (node (ref "U$1") (pin "P$14") (pinfunction "P$14_P$14") (pintype "bidirectional"))
    )
    (net (code "45") (name "Net-(R15-Pad2)") (class "Default")
      (node (ref "R15") (pin "2") (pinfunction "2_2") (pintype "passive"))
      (node (ref "U$1") (pin "P$15") (pinfunction "P$15_P$15") (pintype "bidirectional"))
    )
    (net (code "46") (name "Net-(R16-Pad2)") (class "Default")
      (node (ref "R16") (pin "2") (pinfunction "2_2") (pintype "passive"))
      (node (ref "U$1") (pin "P$16") (pinfunction "P$16_P$16") (pintype "bidirectional"))
    )
    (net (code "47") (name "Net-(R17-Pad2)") (class "Default")
      (node (ref "R17") (pin "2") (pinfunction "2_2") (pintype "passive"))
      (node (ref "U$1") (pin "P$17") (pinfunction "P$17_P$17") (pintype "bidirectional"))
    )
    (net (code "48") (name "Net-(R18-Pad2)") (class "Default")
      (node (ref "R18") (pin "2") (pinfunction "2_2") (pintype "passive"))
      (node (ref "U$1") (pin "P$18") (pinfunction "P$18_P$18") (pintype "bidirectional"))
    )
    (net (code "49") (name "Net-(R19-Pad2)") (class "Default")
      (node (ref "R19") (pin "2") (pinfunction "2_2") (pintype "passive"))
      (node (ref "U$1") (pin "P$19") (pinfunction "P$19_P$19") (pintype "bidirectional"))
    )
    (net (code "50") (name "Net-(R20-Pad2)") (class "Default")
      (node (ref "R20") (pin "2") (pinfunction "2_2") (pintype "passive"))
      (node (ref "U$1") (pin "P$20") (pinfunction "P$20_P$20") (pintype "bidirectional"))
    )
    (net (code "51") (name "Net-(R21-Pad2)") (class "Default")
      (node (ref "R21") (pin "2") (pinfunction "2_2") (pintype "passive"))
      (node (ref "U$1") (pin "P$21") (pinfunction "P$21_P$21") (pintype "bidirectional"))
    )
    (net (code "52") (name "Net-(R22-Pad2)") (class "Default")
      (node (ref "R22") (pin "2") (pinfunction "2_2") (pintype "passive"))
      (node (ref "U$1") (pin "P$39") (pinfunction "P$39_P$39") (pintype "bidirectional"))
    )
    (net (code "53") (name "Net-(R23-Pad2)") (class "Default")
      (node (ref "R23") (pin "2") (pinfunction "2_2") (pintype "passive"))
      (node (ref "U$1") (pin "P$35") (pinfunction "P$35_P$35") (pintype "bidirectional"))
    )
    (net (code "54") (name "Net-(R24-Pad2)") (class "Default")
      (node (ref "R24") (pin "2") (pinfunction "2_2") (pintype "passive"))
      (node (ref "U$1") (pin "P$34") (pinfunction "P$34_P$34") (pintype "bidirectional"))
    )
    (net (code "55") (name "Net-(R25-Pad2)") (class "Default")
      (node (ref "R25") (pin "2") (pinfunction "2_2") (pintype "passive"))
      (node (ref "U$1") (pin "P$33") (pinfunction "P$33_P$33") (pintype "bidirectional"))
    )
    (net (code "56") (name "Net-(R26-Pad2)") (class "Default")
      (node (ref "R26") (pin "2") (pinfunction "2_2") (pintype "passive"))
      (node (ref "U$1") (pin "P$32") (pinfunction "P$32_P$32") (pintype "bidirectional"))
    )
    (net (code "57") (name "Net-(R27-Pad2)") (class "Default")
      (node (ref "R27") (pin "2") (pinfunction "2_2") (pintype "passive"))
      (node (ref "U$1") (pin "P$31") (pinfunction "P$31_P$31") (pintype "bidirectional"))
    )
    (net (code "58") (name "Net-(R28-Pad2)") (class "Default")
      (node (ref "R28") (pin "2") (pinfunction "2_2") (pintype "passive"))
      (node (ref "U$1") (pin "P$30") (pinfunction "P$30_P$30") (pintype "bidirectional"))
    )
    (net (code "59") (name "Net-(R29-Pad2)") (class "Default")
      (node (ref "R29") (pin "2") (pinfunction "2_2") (pintype "passive"))
      (node (ref "U$1") (pin "P$29") (pinfunction "P$29_P$29") (pintype "bidirectional"))
    )
    (net (code "60") (name "Net-(R30-Pad2)") (class "Default")
      (node (ref "R30") (pin "2") (pinfunction "2_2") (pintype "passive"))
      (node (ref "U$1") (pin "P$28") (pinfunction "P$28_P$28") (pintype "bidirectional"))
    )
    (net (code "61") (name "Net-(R31-Pad2)") (class "Default")
      (node (ref "R31") (pin "2") (pinfunction "2_2") (pintype "passive"))
      (node (ref "U$1") (pin "P$27") (pinfunction "P$27_P$27") (pintype "bidirectional"))
    )
    (net (code "62") (name "Net-(R32-Pad2)") (class "Default")
      (node (ref "R32") (pin "2") (pinfunction "2_2") (pintype "passive"))
      (node (ref "U$1") (pin "P$26") (pinfunction "P$26_P$26") (pintype "bidirectional"))
    )
    (net (code "63") (name "Net-(R33-Pad2)") (class "Default")
      (node (ref "R33") (pin "2") (pinfunction "2_2") (pintype "passive"))
      (node (ref "U$1") (pin "P$25") (pinfunction "P$25_P$25") (pintype "bidirectional"))
    )
    (net (code "64") (name "Net-(R34-Pad2)") (class "Default")
      (node (ref "R34") (pin "2") (pinfunction "2_2") (pintype "passive"))
      (node (ref "U$1") (pin "P$24") (pinfunction "P$24_P$24") (pintype "bidirectional"))
    )
    (net (code "65") (name "Net-(R35-Pad2)") (class "Default")
      (node (ref "R35") (pin "2") (pinfunction "2_2") (pintype "passive"))
      (node (ref "U$1") (pin "P$23") (pinfunction "P$23_P$23") (pintype "bidirectional"))
    )
    (net (code "66") (name "Net-(R36-Pad2)") (class "Default")
      (node (ref "R36") (pin "2") (pinfunction "2_2") (pintype "passive"))
      (node (ref "U$1") (pin "P$22") (pinfunction "P$22_P$22") (pintype "bidirectional"))
    )
    (net (code "67") (name "Net-(R37-Pad2)") (class "Default")
      (node (ref "R37") (pin "2") (pinfunction "2_2") (pintype "passive"))
      (node (ref "U$2") (pin "P$4") (pinfunction "P$4_P$4") (pintype "bidirectional"))
    )
    (net (code "68") (name "Net-(R38-Pad2)") (class "Default")
      (node (ref "R38") (pin "2") (pinfunction "2_2") (pintype "passive"))
      (node (ref "U$2") (pin "P$5") (pinfunction "P$5_P$5") (pintype "bidirectional"))
    )
    (net (code "69") (name "Net-(R39-Pad2)") (class "Default")
      (node (ref "R39") (pin "2") (pinfunction "2_2") (pintype "passive"))
      (node (ref "U$2") (pin "P$6") (pinfunction "P$6_P$6") (pintype "bidirectional"))
    )
    (net (code "70") (name "Net-(R40-Pad2)") (class "Default")
      (node (ref "R40") (pin "2") (pinfunction "2_2") (pintype "passive"))
      (node (ref "U$2") (pin "P$7") (pinfunction "P$7_P$7") (pintype "bidirectional"))
    )
    (net (code "71") (name "Net-(R41-Pad2)") (class "Default")
      (node (ref "R41") (pin "2") (pinfunction "2_2") (pintype "passive"))
      (node (ref "U$2") (pin "P$8") (pinfunction "P$8_P$8") (pintype "bidirectional"))
    )
    (net (code "72") (name "Net-(R43-Pad2)") (class "Default")
      (node (ref "R43") (pin "2") (pinfunction "2_2") (pintype "passive"))
      (node (ref "U$2") (pin "P$9") (pinfunction "P$9_P$9") (pintype "bidirectional"))
    )
    (net (code "73") (name "Net-(R44-Pad2)") (class "Default")
      (node (ref "R44") (pin "2") (pinfunction "2_2") (pintype "passive"))
      (node (ref "U$2") (pin "P$10") (pinfunction "P$10_P$10") (pintype "bidirectional"))
    )
    (net (code "74") (name "Net-(R45-Pad2)") (class "Default")
      (node (ref "R45") (pin "2") (pinfunction "2_2") (pintype "passive"))
      (node (ref "U$2") (pin "P$11") (pinfunction "P$11_P$11") (pintype "bidirectional"))
    )
    (net (code "75") (name "Net-(R47-Pad2)") (class "Default")
      (node (ref "R47") (pin "2") (pinfunction "2_2") (pintype "passive"))
      (node (ref "U$2") (pin "P$12") (pinfunction "P$12_P$12") (pintype "bidirectional"))
    )
    (net (code "76") (name "Net-(R48-Pad2)") (class "Default")
      (node (ref "R48") (pin "2") (pinfunction "2_2") (pintype "passive"))
      (node (ref "U$2") (pin "P$13") (pinfunction "P$13_P$13") (pintype "bidirectional"))
    )
    (net (code "77") (name "Net-(R49-Pad2)") (class "Default")
      (node (ref "R49") (pin "2") (pinfunction "2_2") (pintype "passive"))
      (node (ref "U$2") (pin "P$14") (pinfunction "P$14_P$14") (pintype "bidirectional"))
    )
    (net (code "78") (name "Net-(R50-Pad2)") (class "Default")
      (node (ref "R50") (pin "2") (pinfunction "2_2") (pintype "passive"))
      (node (ref "U$2") (pin "P$15") (pinfunction "P$15_P$15") (pintype "bidirectional"))
    )
    (net (code "79") (name "Net-(R51-Pad2)") (class "Default")
      (node (ref "R51") (pin "2") (pinfunction "2_2") (pintype "passive"))
      (node (ref "U$2") (pin "P$16") (pinfunction "P$16_P$16") (pintype "bidirectional"))
    )
    (net (code "80") (name "Net-(R52-Pad2)") (class "Default")
      (node (ref "R52") (pin "2") (pinfunction "2_2") (pintype "passive"))
      (node (ref "U$2") (pin "P$17") (pinfunction "P$17_P$17") (pintype "bidirectional"))
    )
    (net (code "81") (name "Net-(R53-Pad2)") (class "Default")
      (node (ref "R53") (pin "2") (pinfunction "2_2") (pintype "passive"))
      (node (ref "U$2") (pin "P$18") (pinfunction "P$18_P$18") (pintype "bidirectional"))
    )
    (net (code "82") (name "Net-(R54-Pad2)") (class "Default")
      (node (ref "R54") (pin "2") (pinfunction "2_2") (pintype "passive"))
      (node (ref "U$2") (pin "P$19") (pinfunction "P$19_P$19") (pintype "bidirectional"))
    )
    (net (code "83") (name "Net-(R55-Pad2)") (class "Default")
      (node (ref "R55") (pin "2") (pinfunction "2_2") (pintype "passive"))
      (node (ref "U$2") (pin "P$20") (pinfunction "P$20_P$20") (pintype "bidirectional"))
    )
    (net (code "84") (name "Net-(R56-Pad2)") (class "Default")
      (node (ref "R56") (pin "2") (pinfunction "2_2") (pintype "passive"))
      (node (ref "U$2") (pin "P$21") (pinfunction "P$21_P$21") (pintype "bidirectional"))
    )
    (net (code "85") (name "Net-(R57-Pad2)") (class "Default")
      (node (ref "R57") (pin "2") (pinfunction "2_2") (pintype "passive"))
      (node (ref "U$2") (pin "P$39") (pinfunction "P$39_P$39") (pintype "bidirectional"))
    )
    (net (code "86") (name "Net-(R58-Pad2)") (class "Default")
      (node (ref "R58") (pin "2") (pinfunction "2_2") (pintype "passive"))
      (node (ref "U$2") (pin "P$38") (pinfunction "P$38_P$38") (pintype "bidirectional"))
    )
    (net (code "87") (name "Net-(R59-Pad2)") (class "Default")
      (node (ref "R59") (pin "2") (pinfunction "2_2") (pintype "passive"))
      (node (ref "U$2") (pin "P$37") (pinfunction "P$37_P$37") (pintype "bidirectional"))
    )
    (net (code "88") (name "Net-(R60-Pad2)") (class "Default")
      (node (ref "R60") (pin "2") (pinfunction "2_2") (pintype "passive"))
      (node (ref "U$2") (pin "P$36") (pinfunction "P$36_P$36") (pintype "bidirectional"))
    )
    (net (code "89") (name "Net-(R61-Pad2)") (class "Default")
      (node (ref "R61") (pin "2") (pinfunction "2_2") (pintype "passive"))
      (node (ref "U$2") (pin "P$35") (pinfunction "P$35_P$35") (pintype "bidirectional"))
    )
    (net (code "90") (name "Net-(R62-Pad2)") (class "Default")
      (node (ref "R62") (pin "2") (pinfunction "2_2") (pintype "passive"))
      (node (ref "U$2") (pin "P$34") (pinfunction "P$34_P$34") (pintype "bidirectional"))
    )
    (net (code "91") (name "Net-(R63-Pad2)") (class "Default")
      (node (ref "R63") (pin "2") (pinfunction "2_2") (pintype "passive"))
      (node (ref "U$2") (pin "P$33") (pinfunction "P$33_P$33") (pintype "bidirectional"))
    )
    (net (code "92") (name "Net-(R64-Pad2)") (class "Default")
      (node (ref "R64") (pin "2") (pinfunction "2_2") (pintype "passive"))
      (node (ref "U$2") (pin "P$32") (pinfunction "P$32_P$32") (pintype "bidirectional"))
    )
    (net (code "93") (name "Net-(R65-Pad2)") (class "Default")
      (node (ref "R65") (pin "2") (pinfunction "2_2") (pintype "passive"))
      (node (ref "U$2") (pin "P$31") (pinfunction "P$31_P$31") (pintype "bidirectional"))
    )
    (net (code "94") (name "Net-(R66-Pad2)") (class "Default")
      (node (ref "R66") (pin "2") (pinfunction "2_2") (pintype "passive"))
      (node (ref "U$2") (pin "P$30") (pinfunction "P$30_P$30") (pintype "bidirectional"))
    )
    (net (code "95") (name "Net-(R67-Pad2)") (class "Default")
      (node (ref "R67") (pin "2") (pinfunction "2_2") (pintype "passive"))
      (node (ref "U$2") (pin "P$29") (pinfunction "P$29_P$29") (pintype "bidirectional"))
    )
    (net (code "96") (name "Net-(R68-Pad2)") (class "Default")
      (node (ref "R68") (pin "2") (pinfunction "2_2") (pintype "passive"))
      (node (ref "U$2") (pin "P$28") (pinfunction "P$28_P$28") (pintype "bidirectional"))
    )
    (net (code "97") (name "Net-(R69-Pad2)") (class "Default")
      (node (ref "R69") (pin "2") (pinfunction "2_2") (pintype "passive"))
      (node (ref "U$2") (pin "P$27") (pinfunction "P$27_P$27") (pintype "bidirectional"))
    )
    (net (code "98") (name "Net-(R70-Pad2)") (class "Default")
      (node (ref "R70") (pin "2") (pinfunction "2_2") (pintype "passive"))
      (node (ref "U$2") (pin "P$26") (pinfunction "P$26_P$26") (pintype "bidirectional"))
    )
    (net (code "99") (name "Net-(R71-Pad2)") (class "Default")
      (node (ref "R71") (pin "2") (pinfunction "2_2") (pintype "passive"))
      (node (ref "U$2") (pin "P$25") (pinfunction "P$25_P$25") (pintype "bidirectional"))
    )
    (net (code "100") (name "Net-(R72-Pad2)") (class "Default")
      (node (ref "R72") (pin "2") (pinfunction "2_2") (pintype "passive"))
      (node (ref "U$2") (pin "P$24") (pinfunction "P$24_P$24") (pintype "bidirectional"))
    )
    (net (code "101") (name "Net-(R73-Pad2)") (class "Default")
      (node (ref "R73") (pin "2") (pinfunction "2_2") (pintype "passive"))
      (node (ref "U$2") (pin "P$23") (pinfunction "P$23_P$23") (pintype "bidirectional"))
    )
    (net (code "102") (name "Net-(R74-Pad2)") (class "Default")
      (node (ref "R74") (pin "2") (pinfunction "2_2") (pintype "passive"))
      (node (ref "U$2") (pin "P$22") (pinfunction "P$22_P$22") (pintype "bidirectional"))
    )
    (net (code "103") (name "Net-(R77-Pad2)") (class "Default")
      (node (ref "R77") (pin "2") (pinfunction "2_2") (pintype "passive"))
      (node (ref "U$1") (pin "P$1") (pinfunction "P$1_P$1") (pintype "bidirectional"))
    )
    (net (code "104") (name "Net-(R78-Pad2)") (class "Default")
      (node (ref "R78") (pin "2") (pinfunction "2_2") (pintype "passive"))
      (node (ref "U$1") (pin "P$2") (pinfunction "P$2_P$2") (pintype "bidirectional"))
    )
    (net (code "105") (name "Net-(R79-Pad2)") (class "Default")
      (node (ref "R79") (pin "2") (pinfunction "2_2") (pintype "passive"))
      (node (ref "U$1") (pin "P$3") (pinfunction "P$3_P$3") (pintype "bidirectional"))
    )
    (net (code "106") (name "Net-(R80-Pad2)") (class "Default")
      (node (ref "R80") (pin "2") (pinfunction "2_2") (pintype "passive"))
      (node (ref "U$2") (pin "P$1") (pinfunction "P$1_P$1") (pintype "bidirectional"))
    )
    (net (code "107") (name "Net-(R81-Pad2)") (class "Default")
      (node (ref "R81") (pin "2") (pinfunction "2_2") (pintype "passive"))
      (node (ref "U$2") (pin "P$2") (pinfunction "P$2_P$2") (pintype "bidirectional"))
    )
    (net (code "108") (name "Net-(R82-Pad2)") (class "Default")
      (node (ref "R82") (pin "2") (pinfunction "2_2") (pintype "passive"))
      (node (ref "U$2") (pin "P$3") (pinfunction "P$3_P$3") (pintype "bidirectional"))
    )
    (net (code "109") (name "Net-(U1-CS1)") (class "Default")
      (node (ref "R22") (pin "1") (pinfunction "1_1") (pintype "passive"))
      (node (ref "U1") (pin "26") (pinfunction "CS1_26") (pintype "bidirectional"))
    )
    (net (code "110") (name "Net-(U1-CS2)") (class "Default")
      (node (ref "R1") (pin "1") (pinfunction "1_1") (pintype "passive"))
      (node (ref "U1") (pin "27") (pinfunction "CS2_27") (pintype "bidirectional"))
    )
    (net (code "111") (name "Net-(U1-CS3)") (class "Default")
      (node (ref "R2") (pin "1") (pinfunction "1_1") (pintype "passive"))
      (node (ref "U1") (pin "28") (pinfunction "CS3_28") (pintype "bidirectional"))
    )
    (net (code "112") (name "Net-(U1-CS4)") (class "Default")
      (node (ref "R3") (pin "1") (pinfunction "1_1") (pintype "passive"))
      (node (ref "U1") (pin "29") (pinfunction "CS4_29") (pintype "bidirectional"))
    )
    (net (code "113") (name "Net-(U1-CS5)") (class "Default")
      (node (ref "R23") (pin "1") (pinfunction "1_1") (pintype "passive"))
      (node (ref "U1") (pin "30") (pinfunction "CS5_30") (pintype "bidirectional"))
    )
    (net (code "114") (name "Net-(U1-CS6)") (class "Default")
      (node (ref "R24") (pin "1") (pinfunction "1_1") (pintype "passive"))
      (node (ref "U1") (pin "31") (pinfunction "CS6_31") (pintype "bidirectional"))
    )
    (net (code "115") (name "Net-(U1-CS7)") (class "Default")
      (node (ref "R25") (pin "1") (pinfunction "1_1") (pintype "passive"))
      (node (ref "U1") (pin "32") (pinfunction "CS7_32") (pintype "bidirectional"))
    )
    (net (code "116") (name "Net-(U1-CS8)") (class "Default")
      (node (ref "R26") (pin "1") (pinfunction "1_1") (pintype "passive"))
      (node (ref "U1") (pin "33") (pinfunction "CS8_33") (pintype "bidirectional"))
    )
    (net (code "117") (name "Net-(U1-CS9)") (class "Default")
      (node (ref "R27") (pin "1") (pinfunction "1_1") (pintype "passive"))
      (node (ref "U1") (pin "34") (pinfunction "CS9_34") (pintype "bidirectional"))
    )
    (net (code "118") (name "Net-(U1-CS10)") (class "Default")
      (node (ref "R28") (pin "1") (pinfunction "1_1") (pintype "passive"))
      (node (ref "U1") (pin "35") (pinfunction "CS10_35") (pintype "bidirectional"))
    )
    (net (code "119") (name "Net-(U1-CS11)") (class "Default")
      (node (ref "R29") (pin "1") (pinfunction "1_1") (pintype "passive"))
      (node (ref "U1") (pin "37") (pinfunction "CS11_37") (pintype "bidirectional"))
    )
    (net (code "120") (name "Net-(U1-CS12)") (class "Default")
      (node (ref "R30") (pin "1") (pinfunction "1_1") (pintype "passive"))
      (node (ref "U1") (pin "38") (pinfunction "CS12_38") (pintype "bidirectional"))
    )
    (net (code "121") (name "Net-(U1-CS13)") (class "Default")
      (node (ref "R31") (pin "1") (pinfunction "1_1") (pintype "passive"))
      (node (ref "U1") (pin "39") (pinfunction "CS13_39") (pintype "bidirectional"))
    )
    (net (code "122") (name "Net-(U1-CS14)") (class "Default")
      (node (ref "R32") (pin "1") (pinfunction "1_1") (pintype "passive"))
      (node (ref "U1") (pin "40") (pinfunction "CS14_40") (pintype "bidirectional"))
    )
    (net (code "123") (name "Net-(U1-CS15)") (class "Default")
      (node (ref "R33") (pin "1") (pinfunction "1_1") (pintype "passive"))
      (node (ref "U1") (pin "41") (pinfunction "CS15_41") (pintype "bidirectional"))
    )
    (net (code "124") (name "Net-(U1-CS16)") (class "Default")
      (node (ref "R34") (pin "1") (pinfunction "1_1") (pintype "passive"))
      (node (ref "U1") (pin "42") (pinfunction "CS16_42") (pintype "bidirectional"))
    )
    (net (code "125") (name "Net-(U1-CS17)") (class "Default")
      (node (ref "R35") (pin "1") (pinfunction "1_1") (pintype "passive"))
      (node (ref "U1") (pin "43") (pinfunction "CS17_43") (pintype "bidirectional"))
    )
    (net (code "126") (name "Net-(U1-CS18)") (class "Default")
      (node (ref "R36") (pin "1") (pinfunction "1_1") (pintype "passive"))
      (node (ref "U1") (pin "44") (pinfunction "CS18_44") (pintype "bidirectional"))
    )
    (net (code "127") (name "Net-(U1-CS19)") (class "Default")
      (node (ref "R21") (pin "1") (pinfunction "1_1") (pintype "passive"))
      (node (ref "U1") (pin "45") (pinfunction "CS19_45") (pintype "bidirectional"))
    )
    (net (code "128") (name "Net-(U1-CS20)") (class "Default")
      (node (ref "R20") (pin "1") (pinfunction "1_1") (pintype "passive"))
      (node (ref "U1") (pin "46") (pinfunction "CS20_46") (pintype "bidirectional"))
    )
    (net (code "129") (name "Net-(U1-CS21)") (class "Default")
      (node (ref "R19") (pin "1") (pinfunction "1_1") (pintype "passive"))
      (node (ref "U1") (pin "47") (pinfunction "CS21_47") (pintype "bidirectional"))
    )
    (net (code "130") (name "Net-(U1-CS22)") (class "Default")
      (node (ref "R18") (pin "1") (pinfunction "1_1") (pintype "passive"))
      (node (ref "U1") (pin "48") (pinfunction "CS22_48") (pintype "bidirectional"))
    )
    (net (code "131") (name "Net-(U1-CS23)") (class "Default")
      (node (ref "R17") (pin "1") (pinfunction "1_1") (pintype "passive"))
      (node (ref "U1") (pin "49") (pinfunction "CS23_49") (pintype "bidirectional"))
    )
    (net (code "132") (name "Net-(U1-CS24)") (class "Default")
      (node (ref "R16") (pin "1") (pinfunction "1_1") (pintype "passive"))
      (node (ref "U1") (pin "50") (pinfunction "CS24_50") (pintype "bidirectional"))
    )
    (net (code "133") (name "Net-(U1-CS25)") (class "Default")
      (node (ref "R15") (pin "1") (pinfunction "1_1") (pintype "passive"))
      (node (ref "U1") (pin "51") (pinfunction "CS25_51") (pintype "bidirectional"))
    )
    (net (code "134") (name "Net-(U1-CS26)") (class "Default")
      (node (ref "R14") (pin "1") (pinfunction "1_1") (pintype "passive"))
      (node (ref "U1") (pin "52") (pinfunction "CS26_52") (pintype "bidirectional"))
    )
    (net (code "135") (name "Net-(U1-CS27)") (class "Default")
      (node (ref "R13") (pin "1") (pinfunction "1_1") (pintype "passive"))
      (node (ref "U1") (pin "53") (pinfunction "CS27_53") (pintype "bidirectional"))
    )
    (net (code "136") (name "Net-(U1-CS28)") (class "Default")
      (node (ref "R12") (pin "1") (pinfunction "1_1") (pintype "passive"))
      (node (ref "U1") (pin "54") (pinfunction "CS28_54") (pintype "bidirectional"))
    )
    (net (code "137") (name "Net-(U1-CS29)") (class "Default")
      (node (ref "R11") (pin "1") (pinfunction "1_1") (pintype "passive"))
      (node (ref "U1") (pin "56") (pinfunction "CS29_56") (pintype "bidirectional"))
    )
    (net (code "138") (name "Net-(U1-CS30)") (class "Default")
      (node (ref "R10") (pin "1") (pinfunction "1_1") (pintype "passive"))
      (node (ref "U1") (pin "57") (pinfunction "CS30_57") (pintype "bidirectional"))
    )
    (net (code "139") (name "Net-(U1-CS31)") (class "Default")
      (node (ref "R9") (pin "1") (pinfunction "1_1") (pintype "passive"))
      (node (ref "U1") (pin "58") (pinfunction "CS31_58") (pintype "bidirectional"))
    )
    (net (code "140") (name "Net-(U1-CS32)") (class "Default")
      (node (ref "R8") (pin "1") (pinfunction "1_1") (pintype "passive"))
      (node (ref "U1") (pin "59") (pinfunction "CS32_59") (pintype "bidirectional"))
    )
    (net (code "141") (name "Net-(U1-CS33)") (class "Default")
      (node (ref "R7") (pin "1") (pinfunction "1_1") (pintype "passive"))
      (node (ref "U1") (pin "60") (pinfunction "CS33_60") (pintype "bidirectional"))
    )
    (net (code "142") (name "Net-(U1-CS34)") (class "Default")
      (node (ref "R6") (pin "1") (pinfunction "1_1") (pintype "passive"))
      (node (ref "U1") (pin "1") (pinfunction "CS34_1") (pintype "bidirectional"))
    )
    (net (code "143") (name "Net-(U1-CS35)") (class "Default")
      (node (ref "R5") (pin "1") (pinfunction "1_1") (pintype "passive"))
      (node (ref "U1") (pin "2") (pinfunction "CS35_2") (pintype "bidirectional"))
    )
    (net (code "144") (name "Net-(U1-CS36)") (class "Default")
      (node (ref "R4") (pin "1") (pinfunction "1_1") (pintype "passive"))
      (node (ref "U1") (pin "3") (pinfunction "CS36_3") (pintype "bidirectional"))
    )
    (net (code "145") (name "Net-(U1-CS37)") (class "Default")
      (node (ref "R79") (pin "1") (pinfunction "1_1") (pintype "passive"))
      (node (ref "U1") (pin "4") (pinfunction "CS37_4") (pintype "bidirectional"))
    )
    (net (code "146") (name "Net-(U1-CS38)") (class "Default")
      (node (ref "R78") (pin "1") (pinfunction "1_1") (pintype "passive"))
      (node (ref "U1") (pin "5") (pinfunction "CS38_5") (pintype "bidirectional"))
    )
    (net (code "147") (name "Net-(U1-CS39)") (class "Default")
      (node (ref "R77") (pin "1") (pinfunction "1_1") (pintype "passive"))
      (node (ref "U1") (pin "6") (pinfunction "CS39_6") (pintype "bidirectional"))
    )
    (net (code "148") (name "Net-(U1-RSET)") (class "Default")
      (node (ref "R42") (pin "2") (pinfunction "2_2") (pintype "passive"))
      (node (ref "U1") (pin "13") (pinfunction "RSET_13") (pintype "bidirectional"))
    )
    (net (code "149") (name "Net-(U1-SDB)") (class "Default")
      (node (ref "R46") (pin "1") (pinfunction "1_1") (pintype "passive"))
      (node (ref "U1") (pin "11") (pinfunction "SDB_11") (pintype "bidirectional"))
    )
    (net (code "150") (name "Net-(U2-CS1)") (class "Default")
      (node (ref "R57") (pin "1") (pinfunction "1_1") (pintype "passive"))
      (node (ref "U2") (pin "26") (pinfunction "CS1_26") (pintype "bidirectional"))
    )
    (net (code "151") (name "Net-(U2-CS2)") (class "Default")
      (node (ref "R58") (pin "1") (pinfunction "1_1") (pintype "passive"))
      (node (ref "U2") (pin "27") (pinfunction "CS2_27") (pintype "bidirectional"))
    )
    (net (code "152") (name "Net-(U2-CS3)") (class "Default")
      (node (ref "R59") (pin "1") (pinfunction "1_1") (pintype "passive"))
      (node (ref "U2") (pin "28") (pinfunction "CS3_28") (pintype "bidirectional"))
    )
    (net (code "153") (name "Net-(U2-CS4)") (class "Default")
      (node (ref "R60") (pin "1") (pinfunction "1_1") (pintype "passive"))
      (node (ref "U2") (pin "29") (pinfunction "CS4_29") (pintype "bidirectional"))
    )
    (net (code "154") (name "Net-(U2-CS5)") (class "Default")
      (node (ref "R61") (pin "1") (pinfunction "1_1") (pintype "passive"))
      (node (ref "U2") (pin "30") (pinfunction "CS5_30") (pintype "bidirectional"))
    )
    (net (code "155") (name "Net-(U2-CS6)") (class "Default")
      (node (ref "R62") (pin "1") (pinfunction "1_1") (pintype "passive"))
      (node (ref "U2") (pin "31") (pinfunction "CS6_31") (pintype "bidirectional"))
    )
    (net (code "156") (name "Net-(U2-CS7)") (class "Default")
      (node (ref "R63") (pin "1") (pinfunction "1_1") (pintype "passive"))
      (node (ref "U2") (pin "32") (pinfunction "CS7_32") (pintype "bidirectional"))
    )
    (net (code "157") (name "Net-(U2-CS8)") (class "Default")
      (node (ref "R64") (pin "1") (pinfunction "1_1") (pintype "passive"))
      (node (ref "U2") (pin "33") (pinfunction "CS8_33") (pintype "bidirectional"))
    )
    (net (code "158") (name "Net-(U2-CS9)") (class "Default")
      (node (ref "R65") (pin "1") (pinfunction "1_1") (pintype "passive"))
      (node (ref "U2") (pin "34") (pinfunction "CS9_34") (pintype "bidirectional"))
    )
    (net (code "159") (name "Net-(U2-CS10)") (class "Default")
      (node (ref "R66") (pin "1") (pinfunction "1_1") (pintype "passive"))
      (node (ref "U2") (pin "35") (pinfunction "CS10_35") (pintype "bidirectional"))
    )
    (net (code "160") (name "Net-(U2-CS11)") (class "Default")
      (node (ref "R67") (pin "1") (pinfunction "1_1") (pintype "passive"))
      (node (ref "U2") (pin "37") (pinfunction "CS11_37") (pintype "bidirectional"))
    )
    (net (code "161") (name "Net-(U2-CS12)") (class "Default")
      (node (ref "R68") (pin "1") (pinfunction "1_1") (pintype "passive"))
      (node (ref "U2") (pin "38") (pinfunction "CS12_38") (pintype "bidirectional"))
    )
    (net (code "162") (name "Net-(U2-CS13)") (class "Default")
      (node (ref "R69") (pin "1") (pinfunction "1_1") (pintype "passive"))
      (node (ref "U2") (pin "39") (pinfunction "CS13_39") (pintype "bidirectional"))
    )
    (net (code "163") (name "Net-(U2-CS14)") (class "Default")
      (node (ref "R70") (pin "1") (pinfunction "1_1") (pintype "passive"))
      (node (ref "U2") (pin "40") (pinfunction "CS14_40") (pintype "bidirectional"))
    )
    (net (code "164") (name "Net-(U2-CS15)") (class "Default")
      (node (ref "R71") (pin "1") (pinfunction "1_1") (pintype "passive"))
      (node (ref "U2") (pin "41") (pinfunction "CS15_41") (pintype "bidirectional"))
    )
    (net (code "165") (name "Net-(U2-CS16)") (class "Default")
      (node (ref "R72") (pin "1") (pinfunction "1_1") (pintype "passive"))
      (node (ref "U2") (pin "42") (pinfunction "CS16_42") (pintype "bidirectional"))
    )
    (net (code "166") (name "Net-(U2-CS17)") (class "Default")
      (node (ref "R73") (pin "1") (pinfunction "1_1") (pintype "passive"))
      (node (ref "U2") (pin "43") (pinfunction "CS17_43") (pintype "bidirectional"))
    )
    (net (code "167") (name "Net-(U2-CS18)") (class "Default")
      (node (ref "R74") (pin "1") (pinfunction "1_1") (pintype "passive"))
      (node (ref "U2") (pin "44") (pinfunction "CS18_44") (pintype "bidirectional"))
    )
    (net (code "168") (name "Net-(U2-CS19)") (class "Default")
      (node (ref "R56") (pin "1") (pinfunction "1_1") (pintype "passive"))
      (node (ref "U2") (pin "45") (pinfunction "CS19_45") (pintype "bidirectional"))
    )
    (net (code "169") (name "Net-(U2-CS20)") (class "Default")
      (node (ref "R55") (pin "1") (pinfunction "1_1") (pintype "passive"))
      (node (ref "U2") (pin "46") (pinfunction "CS20_46") (pintype "bidirectional"))
    )
    (net (code "170") (name "Net-(U2-CS21)") (class "Default")
      (node (ref "R54") (pin "1") (pinfunction "1_1") (pintype "passive"))
      (node (ref "U2") (pin "47") (pinfunction "CS21_47") (pintype "bidirectional"))
    )
    (net (code "171") (name "Net-(U2-CS22)") (class "Default")
      (node (ref "R53") (pin "1") (pinfunction "1_1") (pintype "passive"))
      (node (ref "U2") (pin "48") (pinfunction "CS22_48") (pintype "bidirectional"))
    )
    (net (code "172") (name "Net-(U2-CS23)") (class "Default")
      (node (ref "R52") (pin "1") (pinfunction "1_1") (pintype "passive"))
      (node (ref "U2") (pin "49") (pinfunction "CS23_49") (pintype "bidirectional"))
    )
    (net (code "173") (name "Net-(U2-CS24)") (class "Default")
      (node (ref "R51") (pin "1") (pinfunction "1_1") (pintype "passive"))
      (node (ref "U2") (pin "50") (pinfunction "CS24_50") (pintype "bidirectional"))
    )
    (net (code "174") (name "Net-(U2-CS25)") (class "Default")
      (node (ref "R50") (pin "1") (pinfunction "1_1") (pintype "passive"))
      (node (ref "U2") (pin "51") (pinfunction "CS25_51") (pintype "bidirectional"))
    )
    (net (code "175") (name "Net-(U2-CS26)") (class "Default")
      (node (ref "R49") (pin "1") (pinfunction "1_1") (pintype "passive"))
      (node (ref "U2") (pin "52") (pinfunction "CS26_52") (pintype "bidirectional"))
    )
    (net (code "176") (name "Net-(U2-CS27)") (class "Default")
      (node (ref "R48") (pin "1") (pinfunction "1_1") (pintype "passive"))
      (node (ref "U2") (pin "53") (pinfunction "CS27_53") (pintype "bidirectional"))
    )
    (net (code "177") (name "Net-(U2-CS28)") (class "Default")
      (node (ref "R47") (pin "1") (pinfunction "1_1") (pintype "passive"))
      (node (ref "U2") (pin "54") (pinfunction "CS28_54") (pintype "bidirectional"))
    )
    (net (code "178") (name "Net-(U2-CS29)") (class "Default")
      (node (ref "R45") (pin "1") (pinfunction "1_1") (pintype "passive"))
      (node (ref "U2") (pin "56") (pinfunction "CS29_56") (pintype "bidirectional"))
    )
    (net (code "179") (name "Net-(U2-CS30)") (class "Default")
      (node (ref "R44") (pin "1") (pinfunction "1_1") (pintype "passive"))
      (node (ref "U2") (pin "57") (pinfunction "CS30_57") (pintype "bidirectional"))
    )
    (net (code "180") (name "Net-(U2-CS31)") (class "Default")
      (node (ref "R43") (pin "1") (pinfunction "1_1") (pintype "passive"))
      (node (ref "U2") (pin "58") (pinfunction "CS31_58") (pintype "bidirectional"))
    )
    (net (code "181") (name "Net-(U2-CS32)") (class "Default")
      (node (ref "R41") (pin "1") (pinfunction "1_1") (pintype "passive"))
      (node (ref "U2") (pin "59") (pinfunction "CS32_59") (pintype "bidirectional"))
    )
    (net (code "182") (name "Net-(U2-CS33)") (class "Default")
      (node (ref "R40") (pin "1") (pinfunction "1_1") (pintype "passive"))
      (node (ref "U2") (pin "60") (pinfunction "CS33_60") (pintype "bidirectional"))
    )
    (net (code "183") (name "Net-(U2-CS34)") (class "Default")
      (node (ref "R39") (pin "1") (pinfunction "1_1") (pintype "passive"))
      (node (ref "U2") (pin "1") (pinfunction "CS34_1") (pintype "bidirectional"))
    )
    (net (code "184") (name "Net-(U2-CS35)") (class "Default")
      (node (ref "R38") (pin "1") (pinfunction "1_1") (pintype "passive"))
      (node (ref "U2") (pin "2") (pinfunction "CS35_2") (pintype "bidirectional"))
    )
    (net (code "185") (name "Net-(U2-CS36)") (class "Default")
      (node (ref "R37") (pin "1") (pinfunction "1_1") (pintype "passive"))
      (node (ref "U2") (pin "3") (pinfunction "CS36_3") (pintype "bidirectional"))
    )
    (net (code "186") (name "Net-(U2-CS37)") (class "Default")
      (node (ref "R82") (pin "1") (pinfunction "1_1") (pintype "passive"))
      (node (ref "U2") (pin "4") (pinfunction "CS37_4") (pintype "bidirectional"))
    )
    (net (code "187") (name "Net-(U2-CS38)") (class "Default")
      (node (ref "R81") (pin "1") (pinfunction "1_1") (pintype "passive"))
      (node (ref "U2") (pin "5") (pinfunction "CS38_5") (pintype "bidirectional"))
    )
    (net (code "188") (name "Net-(U2-CS39)") (class "Default")
      (node (ref "R80") (pin "1") (pinfunction "1_1") (pintype "passive"))
      (node (ref "U2") (pin "6") (pinfunction "CS39_6") (pintype "bidirectional"))
    )
    (net (code "189") (name "Net-(U2-RSET)") (class "Default")
      (node (ref "R75") (pin "2") (pinfunction "2_2") (pintype "passive"))
      (node (ref "U2") (pin "13") (pinfunction "RSET_13") (pintype "bidirectional"))
    )
    (net (code "190") (name "Net-(U2-SDB)") (class "Default")
      (node (ref "R76") (pin "1") (pinfunction "1_1") (pintype "passive"))
      (node (ref "U2") (pin "11") (pinfunction "SDB_11") (pintype "bidirectional"))
    )
    (net (code "191") (name "unconnected-(J2-PadMH1)") (class "Default")
      (node (ref "J2") (pin "MH1") (pinfunction "MH1_MH1") (pintype "bidirectional"))
    )
    (net (code "192") (name "unconnected-(J2-PadMH2)") (class "Default")
      (node (ref "J2") (pin "MH2") (pinfunction "MH2_MH2") (pintype "bidirectional"))
    )
    (net (code "193") (name "unconnected-(J2-PadMH3)") (class "Default")
      (node (ref "J2") (pin "MH3") (pinfunction "MH3_MH3") (pintype "bidirectional"))
    )
    (net (code "194") (name "unconnected-(J2-PadMH4)") (class "Default")
      (node (ref "J2") (pin "MH4") (pinfunction "MH4_MH4") (pintype "bidirectional"))
    )
    (net (code "195") (name "unconnected-(J3-PadMH1)") (class "Default")
      (node (ref "J3") (pin "MH1") (pinfunction "MH1_MH1") (pintype "bidirectional"))
    )
    (net (code "196") (name "unconnected-(J3-PadMH2)") (class "Default")
      (node (ref "J3") (pin "MH2") (pinfunction "MH2_MH2") (pintype "bidirectional"))
    )
    (net (code "197") (name "unconnected-(J3-PadMH3)") (class "Default")
      (node (ref "J3") (pin "MH3") (pinfunction "MH3_MH3") (pintype "bidirectional"))
    )
    (net (code "198") (name "unconnected-(J3-PadMH4)") (class "Default")
      (node (ref "J3") (pin "MH4") (pinfunction "MH4_MH4") (pintype "bidirectional"))
    )
    (net (code "199") (name "unconnected-(U$5-3V3OUT-Pad3V)") (class "Default")
      (node (ref "U$5") (pin "3V") (pinfunction "3V3OUT_3V") (pintype "bidirectional"))
    )
    (net (code "200") (name "unconnected-(U$5-4-PadD4)") (class "Default")
      (node (ref "U$5") (pin "D4") (pinfunction "4_D4") (pintype "bidirectional"))
    )
    (net (code "201") (name "unconnected-(U$5-AREF-PadARF)") (class "Default")
      (node (ref "U$5") (pin "ARF") (pinfunction "AREF_ARF") (pintype "bidirectional"))
    )
    (net (code "202") (name "unconnected-(U$5-Pad11)") (class "Default")
      (node (ref "U$5") (pin "11") (pinfunction "11_11") (pintype "bidirectional"))
    )
    (net (code "203") (name "unconnected-(U$5-Pad12)") (class "Default")
      (node (ref "U$5") (pin "12") (pinfunction "12_12") (pintype "bidirectional"))
    )
    (net (code "204") (name "unconnected-(U$5-Pad13)") (class "Default")
      (node (ref "U$5") (pin "13") (pinfunction "13_13") (pintype "bidirectional"))
    )
    (net (code "205") (name "unconnected-(U$5-PadA0)") (class "Default")
      (node (ref "U$5") (pin "A0") (pinfunction "A0_A0") (pintype "bidirectional"))
    )
    (net (code "206") (name "unconnected-(U$5-PadA1)") (class "Default")
      (node (ref "U$5") (pin "A1") (pinfunction "A1_A1") (pintype "bidirectional"))
    )
    (net (code "207") (name "unconnected-(U$5-PadA2)") (class "Default")
      (node (ref "U$5") (pin "A2") (pinfunction "A2_A2") (pintype "bidirectional"))
    )
    (net (code "208") (name "unconnected-(U$5-PadA3)") (class "Default")
      (node (ref "U$5") (pin "A3") (pinfunction "A3_A3") (pintype "bidirectional"))
    )
    (net (code "209") (name "unconnected-(U$5-PadA4)") (class "Default")
      (node (ref "U$5") (pin "A4") (pinfunction "A4_A4") (pintype "bidirectional"))
    )
    (net (code "210") (name "unconnected-(U$5-PadA5)") (class "Default")
      (node (ref "U$5") (pin "A5") (pinfunction "A5_A5") (pintype "bidirectional"))
    )
    (net (code "211") (name "unconnected-(U$5-PadBAT)") (class "Default")
      (node (ref "U$5") (pin "BAT") (pinfunction "BAT_BAT") (pintype "bidirectional"))
    )
    (net (code "212") (name "unconnected-(U$5-PadEN)") (class "Default")
      (node (ref "U$5") (pin "EN") (pinfunction "EN_EN") (pintype "bidirectional"))
    )
    (net (code "213") (name "unconnected-(U$5-PadMISO)") (class "Default")
      (node (ref "U$5") (pin "MISO") (pinfunction "MISO_MISO") (pintype "bidirectional"))
    )
    (net (code "214") (name "unconnected-(U$5-PadMOSI)") (class "Default")
      (node (ref "U$5") (pin "MOSI") (pinfunction "MOSI_MOSI") (pintype "bidirectional"))
    )
    (net (code "215") (name "unconnected-(U$5-PadRST)") (class "Default")
      (node (ref "U$5") (pin "RST") (pinfunction "RST_RST") (pintype "bidirectional"))
    )
    (net (code "216") (name "unconnected-(U$5-PadSCK)") (class "Default")
      (node (ref "U$5") (pin "SCK") (pinfunction "SCK_SCK") (pintype "bidirectional"))
    )
    (net (code "217") (name "unconnected-(U$5-RX{slash}0-PadRX)") (class "Default")
      (node (ref "U$5") (pin "RX") (pinfunction "RX/0_RX") (pintype "bidirectional"))
    )
    (net (code "218") (name "unconnected-(U$5-TX{slash}1-PadTX)") (class "Default")
      (node (ref "U$5") (pin "TX") (pinfunction "TX/1_TX") (pintype "bidirectional"))
    )
    (net (code "219") (name "unconnected-(U1-INTB-Pad7)") (class "Default")
      (node (ref "U1") (pin "7") (pinfunction "INTB_7") (pintype "bidirectional"))
    )
    (net (code "220") (name "unconnected-(U2-INTB-Pad7)") (class "Default")
      (node (ref "U2") (pin "7") (pinfunction "INTB_7") (pintype "bidirectional"))
    )
  )
)
